# Master.net
KiCad netlist of a schematic drawn in Altium Designer
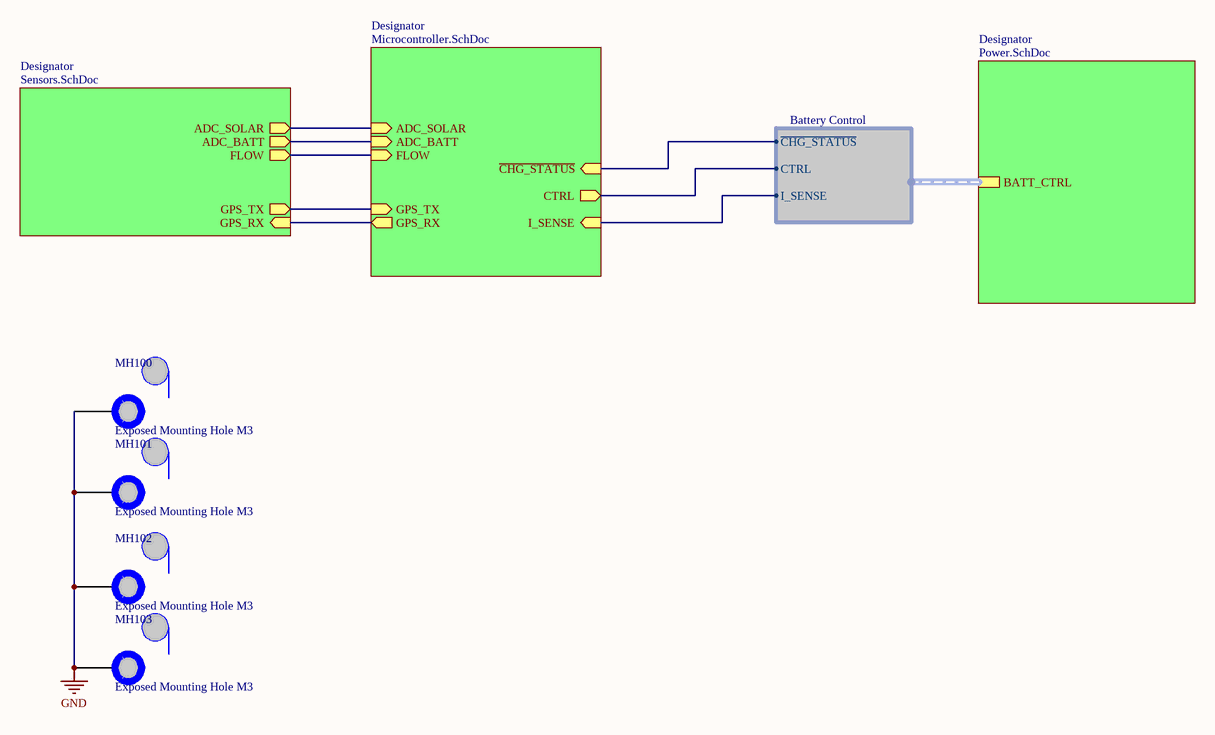
[diagram p0: Master.SchDoc]

(export (version "E")
  (design (tool "Eeschema 10.0.6"))
  (components
    (comp (ref "MH100")
      (value "Exposed Mounting Hole M3")
      (footprint "Mounting Hole M3-Footprint-1")
      (description "M3 Mounting Hole Exposed")
      (libsource (lib "Americas- Environmental Engineering Club- University of Victoria") (part "Mounting Hole M3-Symbol-1"))
    )
    (comp (ref "MH101")
      (value "Exposed Mounting Hole M3")
      (footprint "Mounting Hole M3-Footprint-1")
      (description "M3 Mounting Hole Exposed")
      (libsource (lib "Americas- Environmental Engineering Club- University of Victoria") (part "Mounting Hole M3-Symbol-1"))
    )
    (comp (ref "MH102")
      (value "Exposed Mounting Hole M3")
      (footprint "Mounting Hole M3-Footprint-1")
      (description "M3 Mounting Hole Exposed")
      (libsource (lib "Americas- Environmental Engineering Club- University of Victoria") (part "Mounting Hole M3-Symbol-1"))
    )
    (comp (ref "MH103")
      (value "Exposed Mounting Hole M3")
      (footprint "Mounting Hole M3-Footprint-1")
      (description "M3 Mounting Hole Exposed")
      (libsource (lib "Americas- Environmental Engineering Club- University of Victoria") (part "Mounting Hole M3-Symbol-1"))
    )
  )
  (nets
    (net (code "12") (name "GND") (class "Default")
      (node (ref "MH100") (pin "0") (pinfunction "0_0") (pintype "passive"))
      (node (ref "MH101") (pin "0") (pinfunction "0_0") (pintype "passive"))
      (node (ref "MH102") (pin "0") (pinfunction "0_0") (pintype "passive"))
      (node (ref "MH103") (pin "0") (pinfunction "0_0") (pintype "passive"))
    )
  )
)
